# 12c_extender.net
KiCad netlist of a schematic drawn in EAGLE
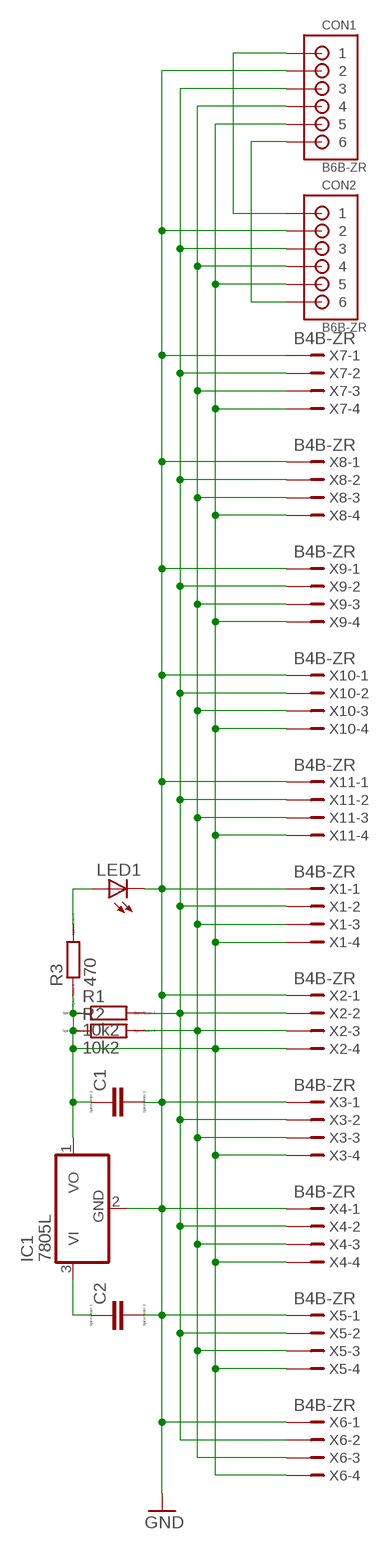
[diagram p0: schematic, sheet 1]

(export (version "E")
  (design (tool "Eeschema 10.0.6"))
  (components
    (comp (ref "C1")
      (value "C-EUC0805")
      (footprint "eagle-import:C0805")
      (libsource (lib "eagle-import") (part "C-EUC0805"))
    )
    (comp (ref "C2")
      (value "C-EUC0805")
      (footprint "eagle-import:C0805")
      (libsource (lib "eagle-import") (part "C-EUC0805"))
    )
    (comp (ref "CON1")
      (value "B6B-ZR")
      (footprint "eagle-import:B6B-ZR")
      (libsource (lib "eagle-import") (part "B6B-ZR"))
    )
    (comp (ref "CON2")
      (value "B6B-ZR")
      (footprint "eagle-import:B6B-ZR")
      (libsource (lib "eagle-import") (part "B6B-ZR"))
    )
    (comp (ref "IC1")
      (value "7805L")
      (footprint "eagle-import:TO92")
      (libsource (lib "eagle-import") (part "78L05"))
    )
    (comp (ref "LED1")
      (value "LEDSMT1206")
      (footprint "eagle-import:1206")
      (libsource (lib "eagle-import") (part "LEDSMT1206"))
    )
    (comp (ref "R1")
      (value "10k2")
      (footprint "eagle-import:R0805")
      (libsource (lib "eagle-import") (part "R-EU_R0805"))
    )
    (comp (ref "R2")
      (value "10k2")
      (footprint "eagle-import:R0805")
      (libsource (lib "eagle-import") (part "R-EU_R0805"))
    )
    (comp (ref "R3")
      (value "470")
      (footprint "eagle-import:R0805")
      (libsource (lib "eagle-import") (part "R-EU_R0805"))
    )
    (comp (ref "X1")
      (value "B4B-ZR")
      (footprint "eagle-import:B4B-ZR")
      (fields (field (name "MF") "FARNELL") (field (name "MPN") "B4B-ZR(LF)(SN)"))
      (libsource (lib "eagle-import") (part "?4B-ZRB"))
    )
    (comp (ref "X2")
      (value "B4B-ZR")
      (footprint "eagle-import:B4B-ZR")
      (fields (field (name "MF") "FARNELL") (field (name "MPN") "B4B-ZR(LF)(SN)"))
      (libsource (lib "eagle-import") (part "?4B-ZRB"))
    )
    (comp (ref "X3")
      (value "B4B-ZR")
      (footprint "eagle-import:B4B-ZR")
      (fields (field (name "MF") "FARNELL") (field (name "MPN") "B4B-ZR(LF)(SN)"))
      (libsource (lib "eagle-import") (part "?4B-ZRB"))
    )
    (comp (ref "X4")
      (value "B4B-ZR")
      (footprint "eagle-import:B4B-ZR")
      (fields (field (name "MF") "FARNELL") (field (name "MPN") "B4B-ZR(LF)(SN)"))
      (libsource (lib "eagle-import") (part "?4B-ZRB"))
    )
    (comp (ref "X5")
      (value "B4B-ZR")
      (footprint "eagle-import:B4B-ZR")
      (fields (field (name "MF") "FARNELL") (field (name "MPN") "B4B-ZR(LF)(SN)"))
      (libsource (lib "eagle-import") (part "?4B-ZRB"))
    )
    (comp (ref "X6")
      (value "B4B-ZR")
      (footprint "eagle-import:B4B-ZR")
      (fields (field (name "MF") "FARNELL") (field (name "MPN") "B4B-ZR(LF)(SN)"))
      (libsource (lib "eagle-import") (part "?4B-ZRB"))
    )
    (comp (ref "X7")
      (value "B4B-ZR")
      (footprint "eagle-import:B4B-ZR")
      (fields (field (name "MF") "FARNELL") (field (name "MPN") "B4B-ZR(LF)(SN)"))
      (libsource (lib "eagle-import") (part "?4B-ZRB"))
    )
    (comp (ref "X8")
      (value "B4B-ZR")
      (footprint "eagle-import:B4B-ZR")
      (fields (field (name "MF") "FARNELL") (field (name "MPN") "B4B-ZR(LF)(SN)"))
      (libsource (lib "eagle-import") (part "?4B-ZRB"))
    )
    (comp (ref "X9")
      (value "B4B-ZR")
      (footprint "eagle-import:B4B-ZR")
      (fields (field (name "MF") "FARNELL") (field (name "MPN") "B4B-ZR(LF)(SN)"))
      (libsource (lib "eagle-import") (part "?4B-ZRB"))
    )
    (comp (ref "X10")
      (value "B4B-ZR")
      (footprint "eagle-import:B4B-ZR")
      (fields (field (name "MF") "FARNELL") (field (name "MPN") "B4B-ZR(LF)(SN)"))
      (libsource (lib "eagle-import") (part "?4B-ZRB"))
    )
    (comp (ref "X11")
      (value "B4B-ZR")
      (footprint "eagle-import:B4B-ZR")
      (fields (field (name "MF") "FARNELL") (field (name "MPN") "B4B-ZR(LF)(SN)"))
      (libsource (lib "eagle-import") (part "?4B-ZRB"))
    )
  )
  (nets
    (net (code "1") (name "GND") (class "Default")
      (node (ref "C1") (pin "2") (pinfunction "2_2") (pintype "passive"))
      (node (ref "C2") (pin "2") (pinfunction "2_2") (pintype "passive"))
      (node (ref "CON1") (pin "2") (pinfunction "2_2") (pintype "bidirectional"))
      (node (ref "CON2") (pin "2") (pinfunction "2_2") (pintype "bidirectional"))
      (node (ref "IC1") (pin "2") (pinfunction "GND_2") (pintype "passive"))
      (node (ref "LED1") (pin "C") (pinfunction "C_C") (pintype "passive"))
      (node (ref "X1") (pin "1") (pinfunction "1_1") (pintype "passive"))
      (node (ref "X10") (pin "1") (pinfunction "1_1") (pintype "passive"))
      (node (ref "X11") (pin "1") (pinfunction "1_1") (pintype "passive"))
      (node (ref "X2") (pin "1") (pinfunction "1_1") (pintype "passive"))
      (node (ref "X3") (pin "1") (pinfunction "1_1") (pintype "passive"))
      (node (ref "X4") (pin "1") (pinfunction "1_1") (pintype "passive"))
      (node (ref "X5") (pin "1") (pinfunction "1_1") (pintype "passive"))
      (node (ref "X6") (pin "1") (pinfunction "1_1") (pintype "passive"))
      (node (ref "X7") (pin "1") (pinfunction "1_1") (pintype "passive"))
      (node (ref "X8") (pin "1") (pinfunction "1_1") (pintype "passive"))
      (node (ref "X9") (pin "1") (pinfunction "1_1") (pintype "passive"))
    )
    (net (code "2") (name "Net-(CON1-Pad1)") (class "Default")
      (node (ref "CON1") (pin "1") (pinfunction "1_1") (pintype "bidirectional"))
      (node (ref "CON2") (pin "1") (pinfunction "1_1") (pintype "bidirectional"))
    )
    (net (code "3") (name "Net-(CON1-Pad6)") (class "Default")
      (node (ref "CON1") (pin "6") (pinfunction "6_6") (pintype "bidirectional"))
      (node (ref "CON2") (pin "6") (pinfunction "6_6") (pintype "bidirectional"))
    )
    (net (code "4") (name "Net-(IC1-VI)") (class "Default")
      (node (ref "C2") (pin "1") (pinfunction "1_1") (pintype "passive"))
      (node (ref "IC1") (pin "3") (pinfunction "VI_3") (pintype "input"))
    )
    (net (code "5") (name "Net-(IC1-VO)") (class "Default")
      (node (ref "C1") (pin "1") (pinfunction "1_1") (pintype "passive"))
      (node (ref "CON1") (pin "5") (pinfunction "5_5") (pintype "bidirectional"))
      (node (ref "CON2") (pin "5") (pinfunction "5_5") (pintype "bidirectional"))
      (node (ref "IC1") (pin "1") (pinfunction "VO_1") (pintype "passive"))
      (node (ref "R1") (pin "1") (pinfunction "1_1") (pintype "passive"))
      (node (ref "R2") (pin "1") (pinfunction "1_1") (pintype "passive"))
      (node (ref "R3") (pin "1") (pinfunction "1_1") (pintype "passive"))
      (node (ref "X1") (pin "4") (pinfunction "1_4") (pintype "passive"))
      (node (ref "X10") (pin "4") (pinfunction "1_4") (pintype "passive"))
      (node (ref "X11") (pin "4") (pinfunction "1_4") (pintype "passive"))
      (node (ref "X2") (pin "4") (pinfunction "1_4") (pintype "passive"))
      (node (ref "X3") (pin "4") (pinfunction "1_4") (pintype "passive"))
      (node (ref "X4") (pin "4") (pinfunction "1_4") (pintype "passive"))
      (node (ref "X5") (pin "4") (pinfunction "1_4") (pintype "passive"))
      (node (ref "X6") (pin "4") (pinfunction "1_4") (pintype "passive"))
      (node (ref "X7") (pin "4") (pinfunction "1_4") (pintype "passive"))
      (node (ref "X8") (pin "4") (pinfunction "1_4") (pintype "passive"))
      (node (ref "X9") (pin "4") (pinfunction "1_4") (pintype "passive"))
    )
    (net (code "6") (name "Net-(LED1-PadA)") (class "Default")
      (node (ref "LED1") (pin "A") (pinfunction "A_A") (pintype "passive"))
      (node (ref "R3") (pin "2") (pinfunction "2_2") (pintype "passive"))
    )
    (net (code "7") (name "Net-(X10B-1)") (class "Default")
      (node (ref "CON1") (pin "3") (pinfunction "3_3") (pintype "bidirectional"))
      (node (ref "CON2") (pin "3") (pinfunction "3_3") (pintype "bidirectional"))
      (node (ref "R1") (pin "2") (pinfunction "2_2") (pintype "passive"))
      (node (ref "X1") (pin "2") (pinfunction "1_2") (pintype "passive"))
      (node (ref "X10") (pin "2") (pinfunction "1_2") (pintype "passive"))
      (node (ref "X11") (pin "2") (pinfunction "1_2") (pintype "passive"))
      (node (ref "X2") (pin "2") (pinfunction "1_2") (pintype "passive"))
      (node (ref "X3") (pin "2") (pinfunction "1_2") (pintype "passive"))
      (node (ref "X4") (pin "2") (pinfunction "1_2") (pintype "passive"))
      (node (ref "X5") (pin "2") (pinfunction "1_2") (pintype "passive"))
      (node (ref "X6") (pin "2") (pinfunction "1_2") (pintype "passive"))
      (node (ref "X7") (pin "2") (pinfunction "1_2") (pintype "passive"))
      (node (ref "X8") (pin "2") (pinfunction "1_2") (pintype "passive"))
      (node (ref "X9") (pin "2") (pinfunction "1_2") (pintype "passive"))
    )
    (net (code "8") (name "Net-(X10C-1)") (class "Default")
      (node (ref "CON1") (pin "4") (pinfunction "4_4") (pintype "bidirectional"))
      (node (ref "CON2") (pin "4") (pinfunction "4_4") (pintype "bidirectional"))
      (node (ref "R2") (pin "2") (pinfunction "2_2") (pintype "passive"))
      (node (ref "X1") (pin "3") (pinfunction "1_3") (pintype "passive"))
      (node (ref "X10") (pin "3") (pinfunction "1_3") (pintype "passive"))
      (node (ref "X11") (pin "3") (pinfunction "1_3") (pintype "passive"))
      (node (ref "X2") (pin "3") (pinfunction "1_3") (pintype "passive"))
      (node (ref "X3") (pin "3") (pinfunction "1_3") (pintype "passive"))
      (node (ref "X4") (pin "3") (pinfunction "1_3") (pintype "passive"))
      (node (ref "X5") (pin "3") (pinfunction "1_3") (pintype "passive"))
      (node (ref "X6") (pin "3") (pinfunction "1_3") (pintype "passive"))
      (node (ref "X7") (pin "3") (pinfunction "1_3") (pintype "passive"))
      (node (ref "X8") (pin "3") (pinfunction "1_3") (pintype "passive"))
      (node (ref "X9") (pin "3") (pinfunction "1_3") (pintype "passive"))
    )
  )
)
